# H_lice31-V_2_2026-04-02.net
KiCad netlist of a schematic drawn in Altium Designer
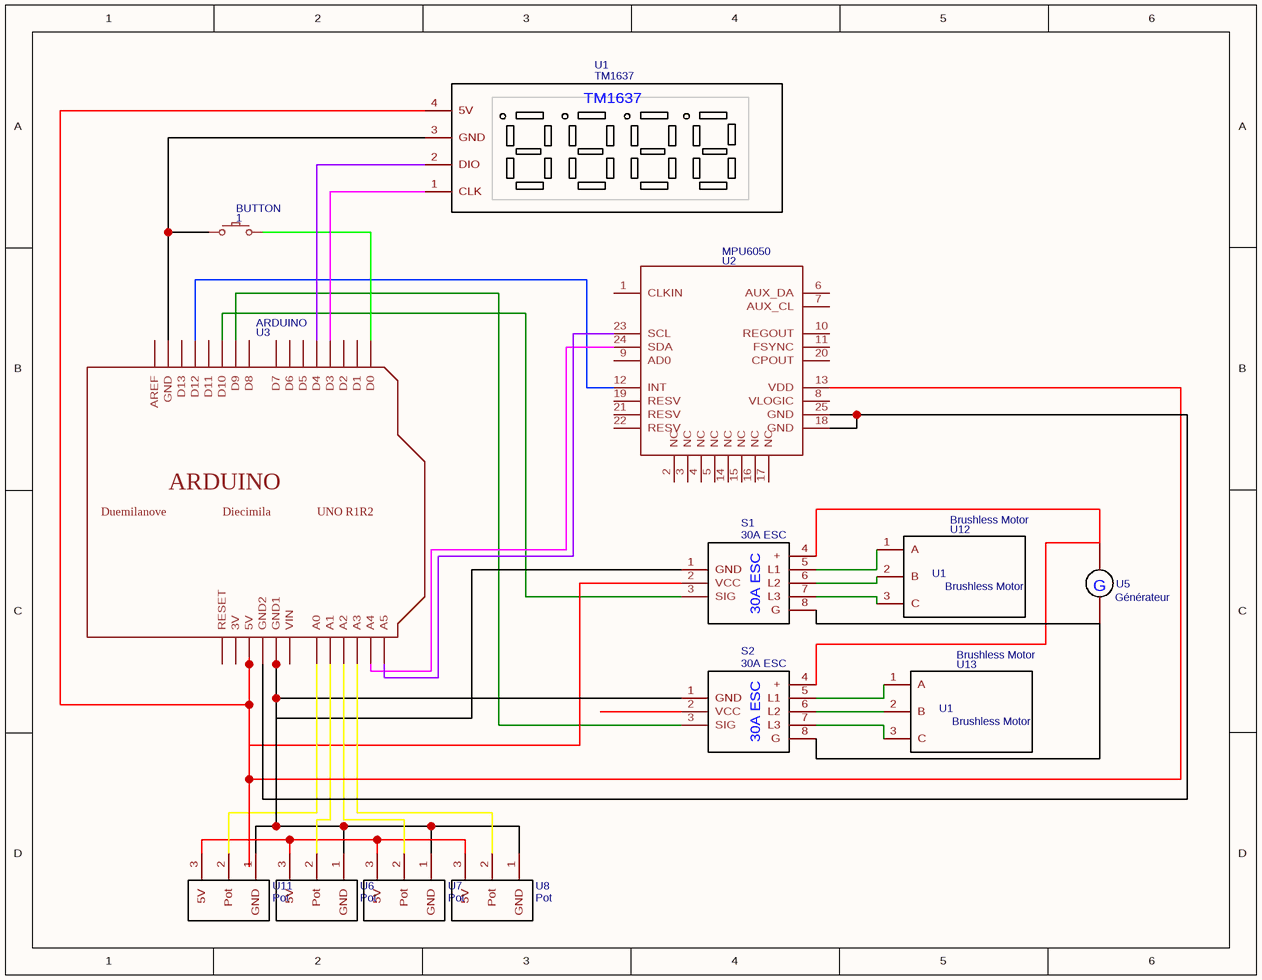
[diagram p0: Hélice31-V.2_2026-04-02.schdoc]

(export (version "E")
  (design (tool "Eeschema 10.0.6"))
  (components
    (comp (ref "1")
      (value "BUTTON")
      (fields (field (name "CONTRIBUTOR") "LorenzoVonMatterhorn"))
      (libsource (lib "altium-import") (part "root_0_BUTTON_"))
    )
    (comp (ref "S1")
      (value "30A ESC")
      (fields (field (name "CONTRIBUTOR") "ilos"))
      (libsource (lib "altium-import") (part "root_3_30A ESC_"))
    )
    (comp (ref "S2")
      (value "30A ESC")
      (fields (field (name "CONTRIBUTOR") "ilos"))
      (libsource (lib "altium-import") (part "root_3_30A ESC_"))
    )
    (comp (ref "U1")
      (value "TM1637")
      (fields (field (name "CONTRIBUTOR") "sensorhost"))
      (libsource (lib "altium-import") (part "root_2_TM1637_"))
    )
    (comp (ref "U2") (value "MPU6050") (libsource (lib "altium-import") (part "root_0_MPU6050_")))
    (comp (ref "U3")
      (value "ARDUINO")
      (fields (field (name "CONTRIBUTOR") "Adafruit"))
      (libsource (lib "altium-import") (part "root_0_ARDUINO_"))
    )
    (comp (ref "U5")
      (value "Générateur")
      (fields (field (name "CONTRIBUTOR") "oswin03"))
      (libsource (lib "altium-import") (part "root_2_Générateur_"))
    )
    (comp (ref "U6")
      (value "Pot")
      (fields (field (name "CONTRIBUTOR") "merlu.timothee"))
      (libsource (lib "altium-import") (part "root_1_Pot_"))
    )
    (comp (ref "U7")
      (value "Pot")
      (fields (field (name "CONTRIBUTOR") "merlu.timothee"))
      (libsource (lib "altium-import") (part "root_1_Pot_"))
    )
    (comp (ref "U8")
      (value "Pot")
      (fields (field (name "CONTRIBUTOR") "merlu.timothee"))
      (libsource (lib "altium-import") (part "root_1_Pot_"))
    )
    (comp (ref "U11")
      (value "Pot")
      (fields (field (name "CONTRIBUTOR") "merlu.timothee"))
      (libsource (lib "altium-import") (part "root_1_Pot_"))
    )
    (comp (ref "U12")
      (value "Brushless Motor")
      (fields (field (name "CONTRIBUTOR") "Droners"))
      (libsource (lib "altium-import") (part "root_0_Brushless Motor_"))
    )
    (comp (ref "U13")
      (value "Brushless Motor")
      (fields (field (name "CONTRIBUTOR") "Droners"))
      (libsource (lib "altium-import") (part "root_0_Brushless Motor_"))
    )
  )
  (nets
    (net (code "1") (name "Net-(1-PadP$ACTIVE)") (class "Default")
      (node (ref "1") (pin "P$ACTIVE") (pinfunction "P$ACTIVE_P$ACTIVE") (pintype "passive"))
      (node (ref "U3") (pin "D0") (pinfunction "D0_D0") (pintype "passive"))
    )
    (net (code "2") (name "Net-(S1-+)") (class "Default")
      (node (ref "S1") (pin "4") (pinfunction "+_4") (pintype "passive"))
      (node (ref "S2") (pin "4") (pinfunction "+_4") (pintype "passive"))
    )
    (net (code "3") (name "Net-(S1-G)") (class "Default")
      (node (ref "S1") (pin "8") (pinfunction "G_8") (pintype "passive"))
      (node (ref "S2") (pin "8") (pinfunction "G_8") (pintype "passive"))
    )
    (net (code "4") (name "Net-(S1-GND)") (class "Default")
      (node (ref "S1") (pin "1") (pinfunction "GND_1") (pintype "passive"))
      (node (ref "S2") (pin "1") (pinfunction "GND_1") (pintype "passive"))
      (node (ref "U11") (pin "1") (pinfunction "GND_1") (pintype "passive"))
      (node (ref "U3") (pin "GND1") (pinfunction "GND1_GND1") (pintype "passive"))
      (node (ref "U6") (pin "1") (pinfunction "GND_1") (pintype "passive"))
      (node (ref "U7") (pin "1") (pinfunction "GND_1") (pintype "passive"))
      (node (ref "U8") (pin "1") (pinfunction "GND_1") (pintype "passive"))
    )
    (net (code "5") (name "Net-(S1-L1)") (class "Default")
      (node (ref "S1") (pin "5") (pinfunction "L1_5") (pintype "passive"))
      (node (ref "U12") (pin "1") (pinfunction "A_1") (pintype "passive"))
    )
    (net (code "6") (name "Net-(S1-L2)") (class "Default")
      (node (ref "S1") (pin "6") (pinfunction "L2_6") (pintype "passive"))
      (node (ref "U12") (pin "2") (pinfunction "B_2") (pintype "passive"))
    )
    (net (code "7") (name "Net-(S1-L3)") (class "Default")
      (node (ref "S1") (pin "7") (pinfunction "L3_7") (pintype "passive"))
      (node (ref "U12") (pin "3") (pinfunction "C_3") (pintype "passive"))
    )
    (net (code "8") (name "Net-(S1-SIG)") (class "Default")
      (node (ref "S1") (pin "3") (pinfunction "SIG_3") (pintype "passive"))
      (node (ref "U3") (pin "D10") (pinfunction "D10_D10") (pintype "passive"))
    )
    (net (code "9") (name "Net-(S1-VCC)") (class "Default")
      (node (ref "S1") (pin "2") (pinfunction "VCC_2") (pintype "passive"))
      (node (ref "U1") (pin "4") (pinfunction "5V_4") (pintype "passive"))
      (node (ref "U2") (pin "13") (pinfunction "VDD_13") (pintype "passive"))
      (node (ref "U3") (pin "5V") (pinfunction "5V_5V") (pintype "passive"))
    )
    (net (code "10") (name "Net-(S2-L1)") (class "Default")
      (node (ref "S2") (pin "5") (pinfunction "L1_5") (pintype "passive"))
      (node (ref "U13") (pin "1") (pinfunction "A_1") (pintype "passive"))
    )
    (net (code "11") (name "Net-(S2-L2)") (class "Default")
      (node (ref "S2") (pin "6") (pinfunction "L2_6") (pintype "passive"))
      (node (ref "U13") (pin "2") (pinfunction "B_2") (pintype "passive"))
    )
    (net (code "12") (name "Net-(S2-L3)") (class "Default")
      (node (ref "S2") (pin "7") (pinfunction "L3_7") (pintype "passive"))
      (node (ref "U13") (pin "3") (pinfunction "C_3") (pintype "passive"))
    )
    (net (code "13") (name "Net-(S2-SIG)") (class "Default")
      (node (ref "S2") (pin "3") (pinfunction "SIG_3") (pintype "passive"))
      (node (ref "U3") (pin "D9") (pinfunction "D9_D9") (pintype "passive"))
    )
    (net (code "14") (name "Net-(U1-CLK)") (class "Default")
      (node (ref "U1") (pin "1") (pinfunction "CLK_1") (pintype "passive"))
      (node (ref "U3") (pin "D3") (pinfunction "D3_D3") (pintype "passive"))
    )
    (net (code "15") (name "Net-(U1-DIO)") (class "Default")
      (node (ref "U1") (pin "2") (pinfunction "DIO_2") (pintype "passive"))
      (node (ref "U3") (pin "D4") (pinfunction "D4_D4") (pintype "passive"))
    )
    (net (code "16") (name "Net-(U1-GND)") (class "Default")
      (node (ref "1") (pin "P$GND") (pinfunction "P$GND_P$GND") (pintype "passive"))
      (node (ref "U1") (pin "3") (pinfunction "GND_3") (pintype "passive"))
      (node (ref "U3") (pin "GND") (pinfunction "GND_GND") (pintype "passive"))
    )
    (net (code "17") (name "Net-(U2-GND-Pad18)") (class "Default")
      (node (ref "U2") (pin "18") (pinfunction "GND_18") (pintype "passive"))
      (node (ref "U2") (pin "25") (pinfunction "GND_25") (pintype "passive"))
      (node (ref "U3") (pin "GND2") (pinfunction "GND2_GND2") (pintype "passive"))
    )
    (net (code "18") (name "Net-(U2-INT)") (class "Default")
      (node (ref "U2") (pin "12") (pinfunction "INT_12") (pintype "passive"))
      (node (ref "U3") (pin "D12") (pinfunction "D12_D12") (pintype "passive"))
    )
    (net (code "19") (name "Net-(U2-SCL)") (class "Default")
      (node (ref "U2") (pin "23") (pinfunction "SCL_23") (pintype "passive"))
      (node (ref "U3") (pin "A5") (pinfunction "A5_A5") (pintype "passive"))
    )
    (net (code "20") (name "Net-(U2-SDA)") (class "Default")
      (node (ref "U2") (pin "24") (pinfunction "SDA_24") (pintype "passive"))
      (node (ref "U3") (pin "A4") (pinfunction "A4_A4") (pintype "passive"))
    )
    (net (code "21") (name "Net-(U6-Pot)") (class "Default")
      (node (ref "U3") (pin "A1") (pinfunction "A1_A1") (pintype "passive"))
      (node (ref "U6") (pin "2") (pinfunction "Pot_2") (pintype "passive"))
    )
    (net (code "22") (name "Net-(U7-Pot)") (class "Default")
      (node (ref "U3") (pin "A2") (pinfunction "A2_A2") (pintype "passive"))
      (node (ref "U7") (pin "2") (pinfunction "Pot_2") (pintype "passive"))
    )
    (net (code "23") (name "Net-(U8-Pot)") (class "Default")
      (node (ref "U3") (pin "A3") (pinfunction "A3_A3") (pintype "passive"))
      (node (ref "U8") (pin "2") (pinfunction "Pot_2") (pintype "passive"))
    )
    (net (code "24") (name "Net-(U11-5V)") (class "Default")
      (node (ref "U11") (pin "3") (pinfunction "5V_3") (pintype "passive"))
      (node (ref "U6") (pin "3") (pinfunction "5V_3") (pintype "passive"))
      (node (ref "U7") (pin "3") (pinfunction "5V_3") (pintype "passive"))
      (node (ref "U8") (pin "3") (pinfunction "5V_3") (pintype "passive"))
    )
    (net (code "25") (name "Net-(U11-Pot)") (class "Default")
      (node (ref "U11") (pin "2") (pinfunction "Pot_2") (pintype "passive"))
      (node (ref "U3") (pin "A0") (pinfunction "A0_A0") (pintype "passive"))
    )
    (net (code "26") (name "unconnected-(S2-VCC-Pad2)") (class "Default")
      (node (ref "S2") (pin "2") (pinfunction "VCC_2") (pintype "passive"))
    )
    (net (code "27") (name "unconnected-(U2-AD0-Pad9)") (class "Default")
      (node (ref "U2") (pin "9") (pinfunction "AD0_9") (pintype "passive"))
    )
    (net (code "28") (name "unconnected-(U2-AUX_CL-Pad7)") (class "Default")
      (node (ref "U2") (pin "7") (pinfunction "AUX_CL_7") (pintype "passive"))
    )
    (net (code "29") (name "unconnected-(U2-AUX_DA-Pad6)") (class "Default")
      (node (ref "U2") (pin "6") (pinfunction "AUX_DA_6") (pintype "passive"))
    )
    (net (code "30") (name "unconnected-(U2-CLKIN-Pad1)") (class "Default")
      (node (ref "U2") (pin "1") (pinfunction "CLKIN_1") (pintype "passive"))
    )
    (net (code "31") (name "unconnected-(U2-CPOUT-Pad20)") (class "Default")
      (node (ref "U2") (pin "20") (pinfunction "CPOUT_20") (pintype "passive"))
    )
    (net (code "32") (name "unconnected-(U2-FSYNC-Pad11)") (class "Default")
      (node (ref "U2") (pin "11") (pinfunction "FSYNC_11") (pintype "passive"))
    )
    (net (code "33") (name "unconnected-(U2-NC-Pad2)") (class "Default")
      (node (ref "U2") (pin "2") (pinfunction "NC_2") (pintype "passive"))
    )
    (net (code "34") (name "unconnected-(U2-NC-Pad3)") (class "Default")
      (node (ref "U2") (pin "3") (pinfunction "NC_3") (pintype "passive"))
    )
    (net (code "35") (name "unconnected-(U2-NC-Pad4)") (class "Default")
      (node (ref "U2") (pin "4") (pinfunction "NC_4") (pintype "passive"))
    )
    (net (code "36") (name "unconnected-(U2-NC-Pad5)") (class "Default")
      (node (ref "U2") (pin "5") (pinfunction "NC_5") (pintype "passive"))
    )
    (net (code "37") (name "unconnected-(U2-NC-Pad14)") (class "Default")
      (node (ref "U2") (pin "14") (pinfunction "NC_14") (pintype "passive"))
    )
    (net (code "38") (name "unconnected-(U2-NC-Pad15)") (class "Default")
      (node (ref "U2") (pin "15") (pinfunction "NC_15") (pintype "passive"))
    )
    (net (code "39") (name "unconnected-(U2-NC-Pad16)") (class "Default")
      (node (ref "U2") (pin "16") (pinfunction "NC_16") (pintype "passive"))
    )
    (net (code "40") (name "unconnected-(U2-NC-Pad17)") (class "Default")
      (node (ref "U2") (pin "17") (pinfunction "NC_17") (pintype "passive"))
    )
    (net (code "41") (name "unconnected-(U2-REGOUT-Pad10)") (class "Default")
      (node (ref "U2") (pin "10") (pinfunction "REGOUT_10") (pintype "passive"))
    )
    (net (code "42") (name "unconnected-(U2-RESV-Pad19)") (class "Default")
      (node (ref "U2") (pin "19") (pinfunction "RESV_19") (pintype "passive"))
    )
    (net (code "43") (name "unconnected-(U2-RESV-Pad21)") (class "Default")
      (node (ref "U2") (pin "21") (pinfunction "RESV_21") (pintype "passive"))
    )
    (net (code "44") (name "unconnected-(U2-RESV-Pad22)") (class "Default")
      (node (ref "U2") (pin "22") (pinfunction "RESV_22") (pintype "passive"))
    )
    (net (code "45") (name "unconnected-(U2-VLOGIC-Pad8)") (class "Default")
      (node (ref "U2") (pin "8") (pinfunction "VLOGIC_8") (pintype "passive"))
    )
    (net (code "46") (name "unconnected-(U3-Pad3V)") (class "Default")
      (node (ref "U3") (pin "3V") (pinfunction "3V_3V") (pintype "passive"))
    )
    (net (code "47") (name "unconnected-(U3-PadAREF)") (class "Default")
      (node (ref "U3") (pin "AREF") (pinfunction "AREF_AREF") (pintype "passive"))
    )
    (net (code "48") (name "unconnected-(U3-PadD1)") (class "Default")
      (node (ref "U3") (pin "D1") (pinfunction "D1_D1") (pintype "passive"))
    )
    (net (code "49") (name "unconnected-(U3-PadD2)") (class "Default")
      (node (ref "U3") (pin "D2") (pinfunction "D2_D2") (pintype "passive"))
    )
    (net (code "50") (name "unconnected-(U3-PadD5)") (class "Default")
      (node (ref "U3") (pin "D5") (pinfunction "D5_D5") (pintype "passive"))
    )
    (net (code "51") (name "unconnected-(U3-PadD6)") (class "Default")
      (node (ref "U3") (pin "D6") (pinfunction "D6_D6") (pintype "passive"))
    )
    (net (code "52") (name "unconnected-(U3-PadD7)") (class "Default")
      (node (ref "U3") (pin "D7") (pinfunction "D7_D7") (pintype "passive"))
    )
    (net (code "53") (name "unconnected-(U3-PadD8)") (class "Default")
      (node (ref "U3") (pin "D8") (pinfunction "D8_D8") (pintype "passive"))
    )
    (net (code "54") (name "unconnected-(U3-PadD11)") (class "Default")
      (node (ref "U3") (pin "D11") (pinfunction "D11_D11") (pintype "passive"))
    )
    (net (code "55") (name "unconnected-(U3-PadD13)") (class "Default")
      (node (ref "U3") (pin "D13") (pinfunction "D13_D13") (pintype "passive"))
    )
    (net (code "56") (name "unconnected-(U3-PadRESET)") (class "Default")
      (node (ref "U3") (pin "RESET") (pinfunction "RESET_RESET") (pintype "passive"))
    )
    (net (code "57") (name "unconnected-(U3-PadVIN)") (class "Default")
      (node (ref "U3") (pin "VIN") (pinfunction "VIN_VIN") (pintype "passive"))
    )
    (net (code "58") (name "unconnected-(U5-Pad1)") (class "Default")
      (node (ref "U5") (pin "1") (pinfunction "1_1") (pintype "passive"))
    )
    (net (code "59") (name "unconnected-(U5-Pad2)") (class "Default")
      (node (ref "U5") (pin "2") (pinfunction "2_2") (pintype "passive"))
    )
  )
)
